# cpu-68008.net
KiCad netlist of a schematic drawn in EAGLE
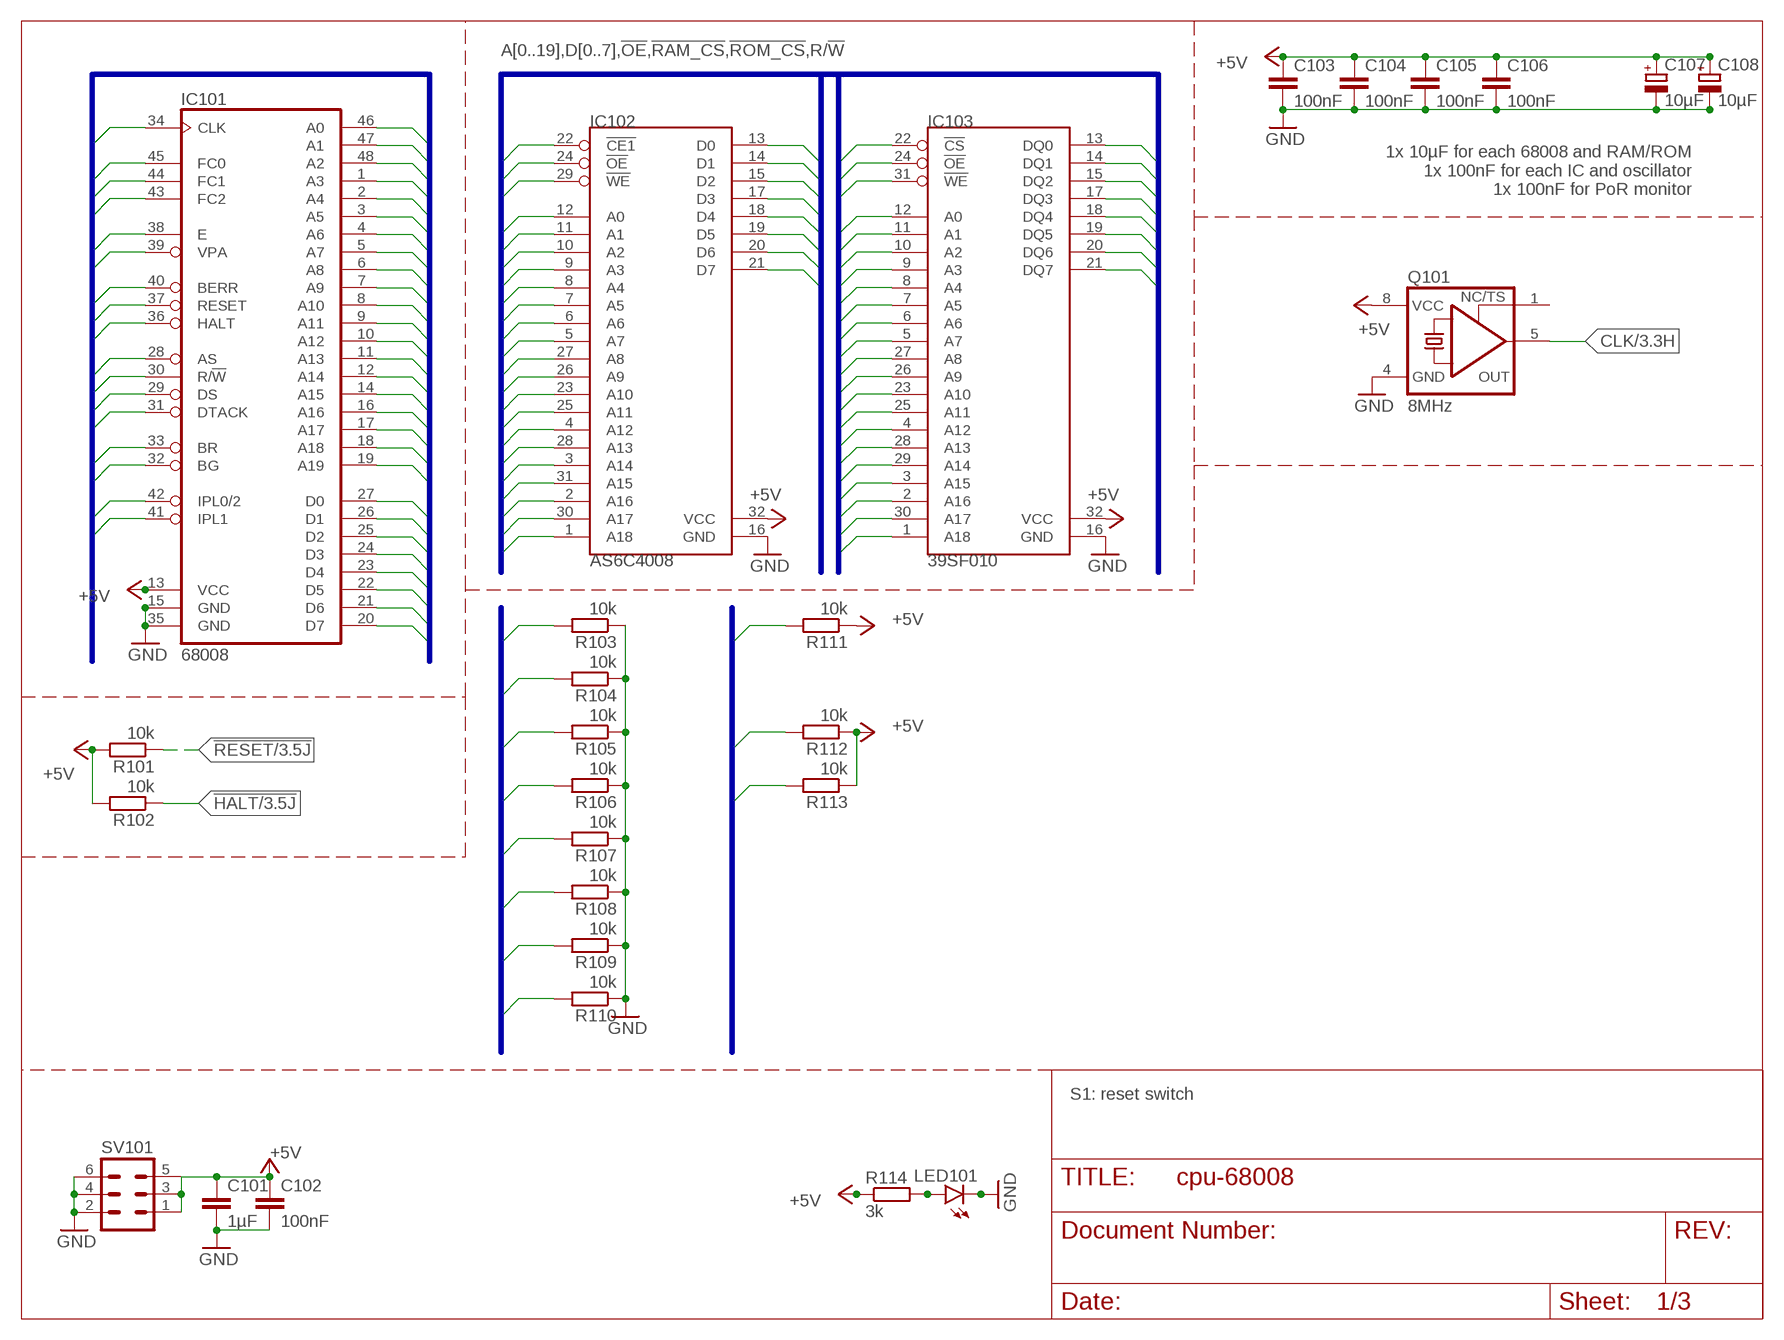
[diagram p0: schematic, sheet 1]
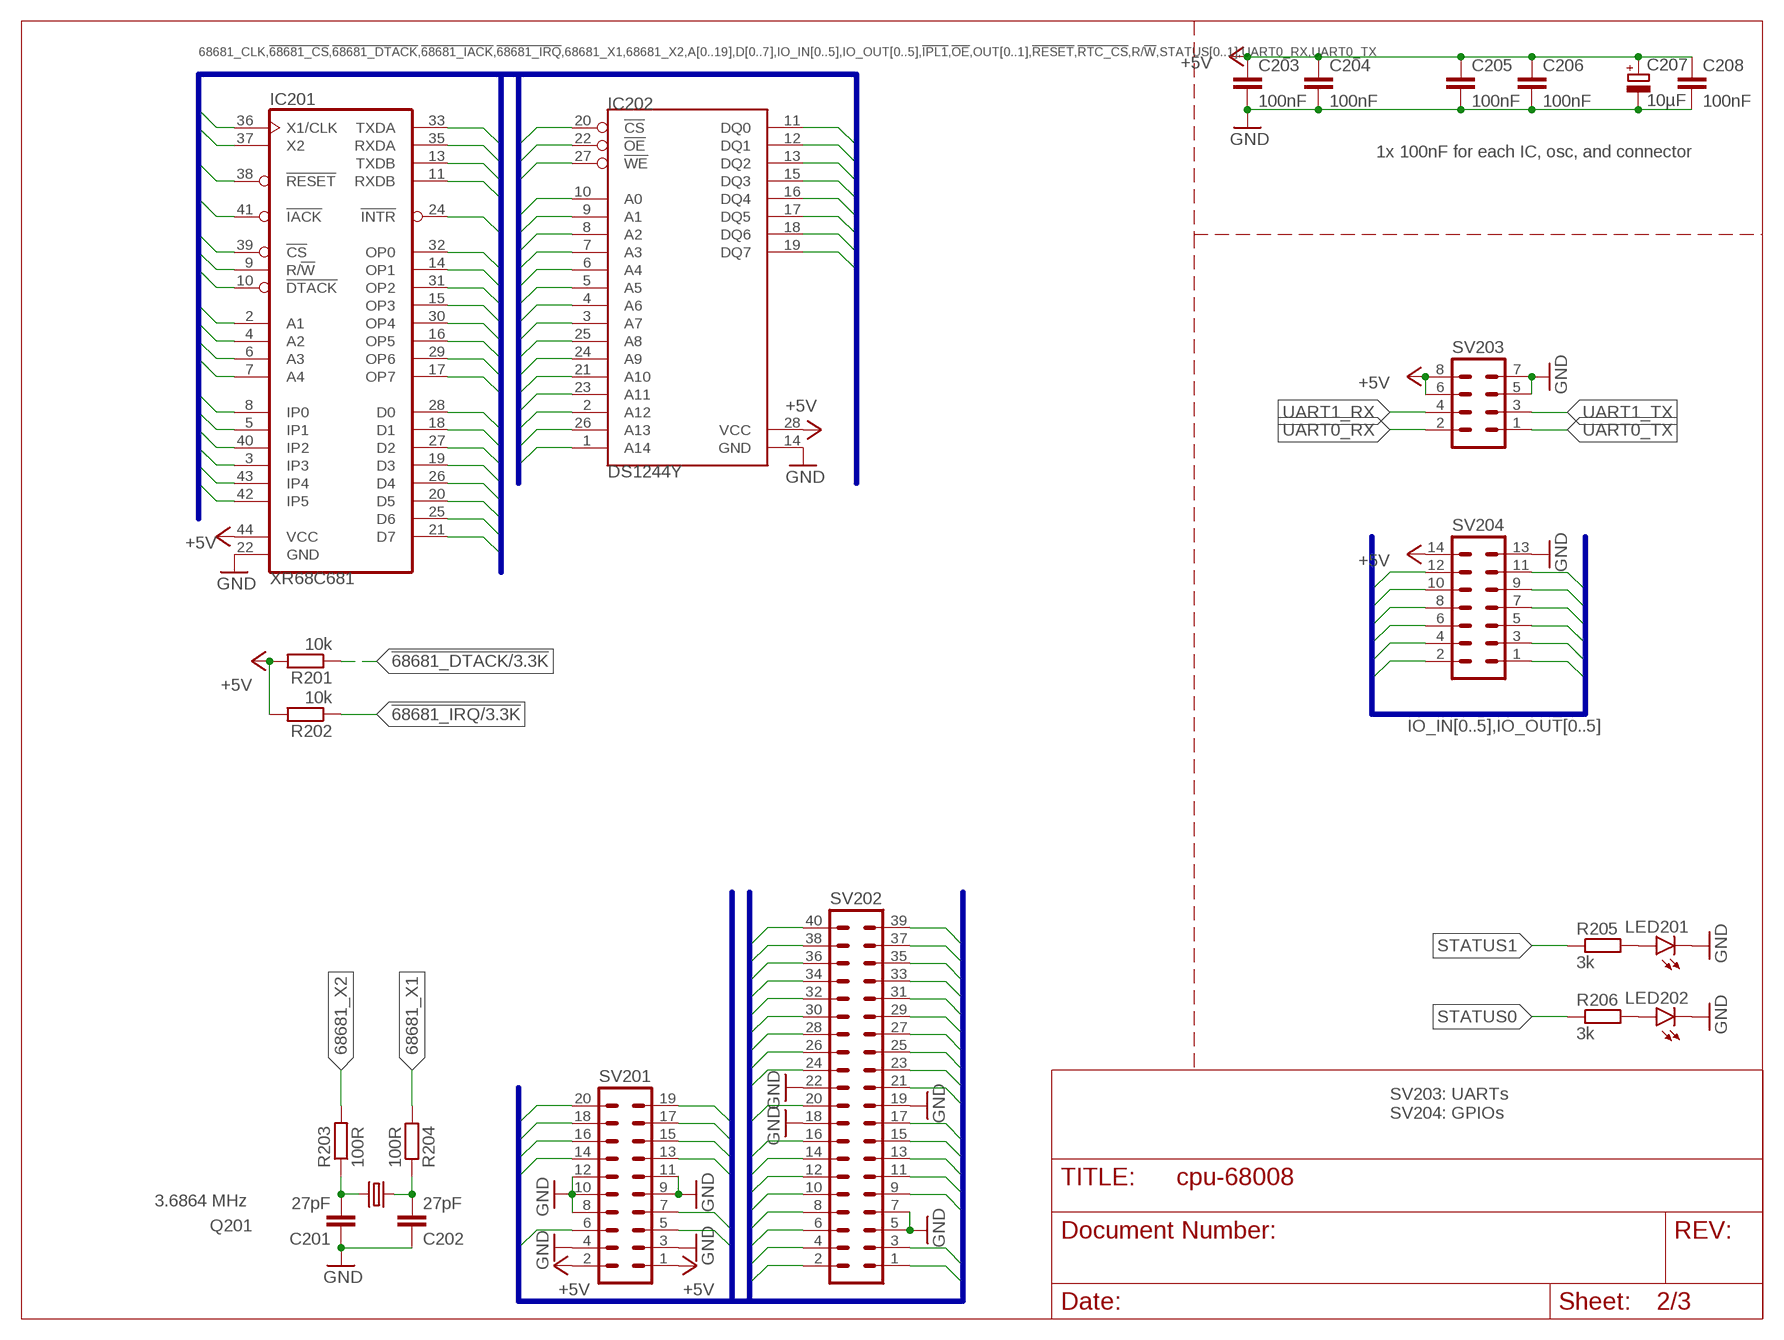
[diagram p1: schematic, sheet 2]
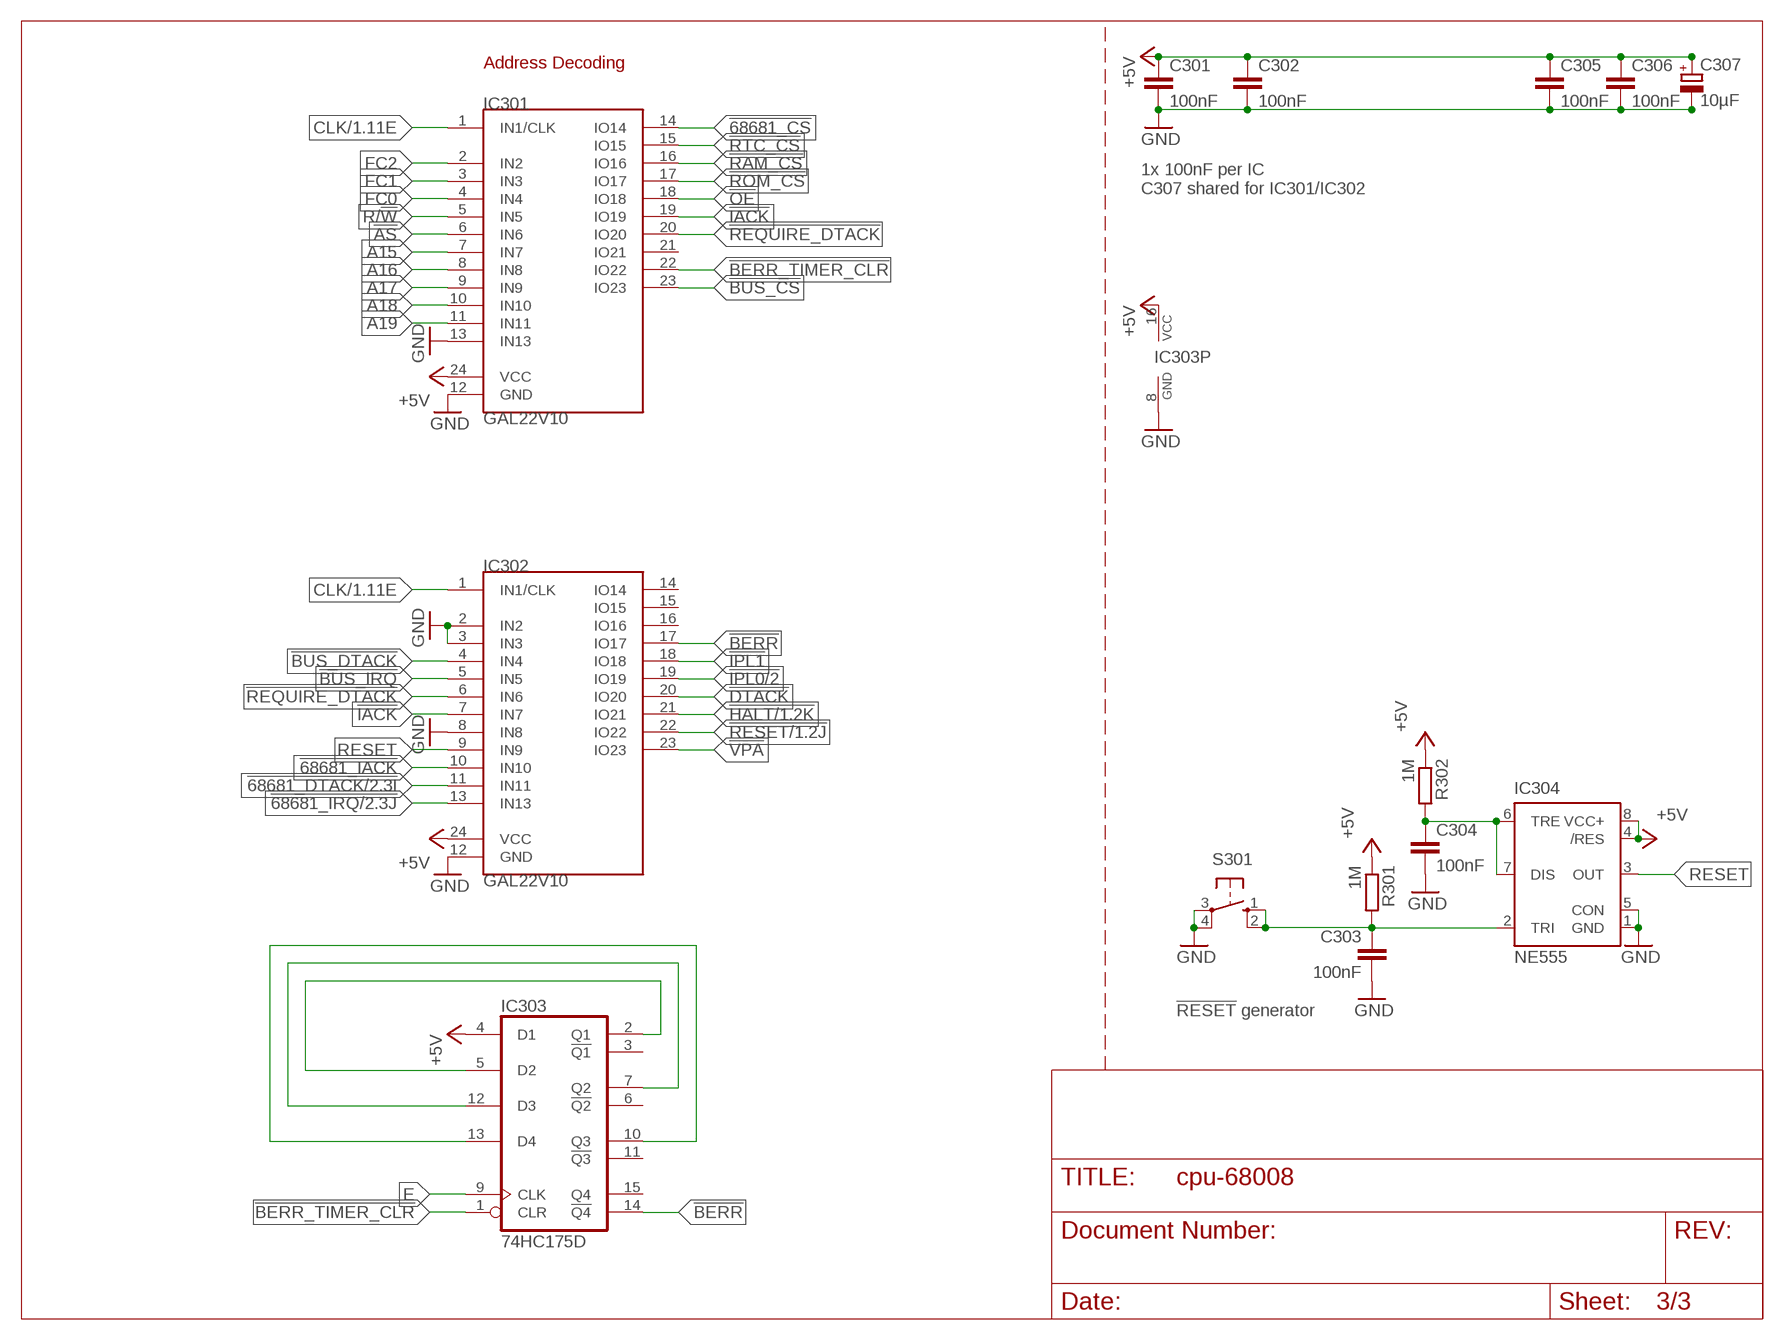
[diagram p2: schematic, sheet 3]

(export (version "E")
  (design (tool "Eeschema 10.0.6"))
  (components
    (comp (ref "C301")
      (value "100nF")
      (footprint "eagle-import:C0805")
      (libsource (lib "eagle-import") (part "C-EUC0805"))
    )
    (comp (ref "C302")
      (value "100nF")
      (footprint "eagle-import:C0805")
      (libsource (lib "eagle-import") (part "C-EUC0805"))
    )
    (comp (ref "C303")
      (value "100nF")
      (footprint "eagle-import:C0805")
      (libsource (lib "eagle-import") (part "C-EUC0805"))
    )
    (comp (ref "C304")
      (value "100nF")
      (footprint "eagle-import:C0805")
      (libsource (lib "eagle-import") (part "C-EUC0805"))
    )
    (comp (ref "C305")
      (value "100nF")
      (footprint "eagle-import:C0805")
      (libsource (lib "eagle-import") (part "C-EUC0805"))
    )
    (comp (ref "C306")
      (value "100nF")
      (footprint "eagle-import:C0805")
      (libsource (lib "eagle-import") (part "C-EUC0805"))
    )
    (comp (ref "C307")
      (value "10µF")
      (footprint "eagle-import:SMC_B")
      (libsource (lib "eagle-import") (part "CPOL-EUSMCB"))
    )
    (comp (ref "IC301")
      (value "GAL22V10")
      (footprint "eagle-import:DIL24S")
      (libsource (lib "eagle-import") (part "GAL22V10DIP24"))
    )
    (comp (ref "IC302")
      (value "GAL22V10")
      (footprint "eagle-import:DIL24S")
      (libsource (lib "eagle-import") (part "GAL22V10DIP24"))
    )
    (comp (ref "IC303")
      (value "74HC175D")
      (footprint "eagle-import:SO16")
      (libsource (lib "eagle-import") (part "74175DHC"))
    )
    (comp (ref "IC304")
      (value "NE555")
      (footprint "eagle-import:DIL-08")
      (fields (field (name "MF") "Arrow Electronics") (field (name "MPN") "NE555N"))
      (libsource (lib "eagle-import") (part "NE555"))
    )
    (comp (ref "R301")
      (value "1M")
      (footprint "eagle-import:R2012")
      (libsource (lib "eagle-import") (part "R-EU_R2012"))
    )
    (comp (ref "R302")
      (value "1M")
      (footprint "eagle-import:R2012")
      (libsource (lib "eagle-import") (part "R-EU_R2012"))
    )
    (comp (ref "S301")
      (value "10-XX")
      (footprint "eagle-import:B3F-10XX")
      (fields (field (name "MPN") "B3F-1000"))
      (libsource (lib "eagle-import") (part "10-XX"))
    )
    (comp (ref "C101")
      (value "1µF")
      (footprint "eagle-import:C0805")
      (libsource (lib "eagle-import") (part "C-EUC0805"))
    )
    (comp (ref "C102")
      (value "100nF")
      (footprint "eagle-import:C0805")
      (libsource (lib "eagle-import") (part "C-EUC0805"))
    )
    (comp (ref "C103")
      (value "100nF")
      (footprint "eagle-import:C0805")
      (libsource (lib "eagle-import") (part "C-EUC0805"))
    )
    (comp (ref "C104")
      (value "100nF")
      (footprint "eagle-import:C0805")
      (libsource (lib "eagle-import") (part "C-EUC0805"))
    )
    (comp (ref "C105")
      (value "100nF")
      (footprint "eagle-import:C0805")
      (libsource (lib "eagle-import") (part "C-EUC0805"))
    )
    (comp (ref "C106")
      (value "100nF")
      (footprint "eagle-import:C0805")
      (libsource (lib "eagle-import") (part "C-EUC0805"))
    )
    (comp (ref "C107")
      (value "10µF")
      (footprint "eagle-import:SMC_B")
      (libsource (lib "eagle-import") (part "CPOL-EUSMCB"))
    )
    (comp (ref "C108")
      (value "10µF")
      (footprint "eagle-import:SMC_B")
      (libsource (lib "eagle-import") (part "CPOL-EUSMCB"))
    )
    (comp (ref "IC101")
      (value "68008")
      (footprint "eagle-import:DIL48")
      (libsource (lib "eagle-import") (part "MC68008P"))
    )
    (comp (ref "IC102")
      (value "AS6C4008")
      (footprint "eagle-import:DIL32")
      (libsource (lib "eagle-import") (part "AS6C4008"))
    )
    (comp (ref "IC103")
      (value "39SF010")
      (footprint "eagle-import:DIL32")
      (fields (field (name "MOUSER") "804-39SF010A7CPHE"))
      (libsource (lib "eagle-import") (part "SST39SF0X0PDIP32"))
    )
    (comp (ref "LED101")
      (value "LEDCHIPLED_1206")
      (footprint "eagle-import:CHIPLED_1206")
      (libsource (lib "eagle-import") (part "LEDCHIPLED_1206"))
    )
    (comp (ref "Q101")
      (value "8MHz")
      (footprint "eagle-import:DIL08S")
      (libsource (lib "eagle-import") (part "XO-8"))
    )
    (comp (ref "R101")
      (value "10k")
      (footprint "eagle-import:R2012")
      (libsource (lib "eagle-import") (part "R-EU_R2012"))
    )
    (comp (ref "R102")
      (value "10k")
      (footprint "eagle-import:R2012")
      (libsource (lib "eagle-import") (part "R-EU_R2012"))
    )
    (comp (ref "R103")
      (value "10k")
      (footprint "eagle-import:R2012")
      (libsource (lib "eagle-import") (part "R-EU_R2012"))
    )
    (comp (ref "R104")
      (value "10k")
      (footprint "eagle-import:R2012")
      (libsource (lib "eagle-import") (part "R-EU_R2012"))
    )
    (comp (ref "R105")
      (value "10k")
      (footprint "eagle-import:R2012")
      (libsource (lib "eagle-import") (part "R-EU_R2012"))
    )
    (comp (ref "R106")
      (value "10k")
      (footprint "eagle-import:R2012")
      (libsource (lib "eagle-import") (part "R-EU_R2012"))
    )
    (comp (ref "R107")
      (value "10k")
      (footprint "eagle-import:R2012")
      (libsource (lib "eagle-import") (part "R-EU_R2012"))
    )
    (comp (ref "R108")
      (value "10k")
      (footprint "eagle-import:R2012")
      (libsource (lib "eagle-import") (part "R-EU_R2012"))
    )
    (comp (ref "R109")
      (value "10k")
      (footprint "eagle-import:R2012")
      (libsource (lib "eagle-import") (part "R-EU_R2012"))
    )
    (comp (ref "R110")
      (value "10k")
      (footprint "eagle-import:R2012")
      (libsource (lib "eagle-import") (part "R-EU_R2012"))
    )
    (comp (ref "R111")
      (value "10k")
      (footprint "eagle-import:R2012")
      (libsource (lib "eagle-import") (part "R-EU_R2012"))
    )
    (comp (ref "R112")
      (value "10k")
      (footprint "eagle-import:R2012")
      (libsource (lib "eagle-import") (part "R-EU_R2012"))
    )
    (comp (ref "R113")
      (value "10k")
      (footprint "eagle-import:R2012")
      (libsource (lib "eagle-import") (part "R-EU_R2012"))
    )
    (comp (ref "R114")
      (value "3k")
      (footprint "eagle-import:R2012")
      (libsource (lib "eagle-import") (part "R-EU_R2012"))
    )
    (comp (ref "SV101")
      (value "MA03-2")
      (footprint "eagle-import:MA03-2")
      (libsource (lib "eagle-import") (part "MA03-2"))
    )
    (comp (ref "C201")
      (value "27pF")
      (footprint "eagle-import:C0805")
      (libsource (lib "eagle-import") (part "C-EUC0805"))
    )
    (comp (ref "C202")
      (value "27pF")
      (footprint "eagle-import:C0805")
      (libsource (lib "eagle-import") (part "C-EUC0805"))
    )
    (comp (ref "C203")
      (value "100nF")
      (footprint "eagle-import:C0805")
      (libsource (lib "eagle-import") (part "C-EUC0805"))
    )
    (comp (ref "C204")
      (value "100nF")
      (footprint "eagle-import:C0805")
      (libsource (lib "eagle-import") (part "C-EUC0805"))
    )
    (comp (ref "C205")
      (value "100nF")
      (footprint "eagle-import:C0805")
      (libsource (lib "eagle-import") (part "C-EUC0805"))
    )
    (comp (ref "C206")
      (value "100nF")
      (footprint "eagle-import:C0805")
      (libsource (lib "eagle-import") (part "C-EUC0805"))
    )
    (comp (ref "C207")
      (value "10µF")
      (footprint "eagle-import:SMC_B")
      (libsource (lib "eagle-import") (part "CPOL-EUSMCB"))
    )
    (comp (ref "C208")
      (value "100nF")
      (footprint "eagle-import:C0805")
      (libsource (lib "eagle-import") (part "C-EUC0805"))
    )
    (comp (ref "IC201")
      (value "XR68C681")
      (footprint "eagle-import:PLCC-S44")
      (libsource (lib "eagle-import") (part "MC68681PLCC44-SOCKET"))
    )
    (comp (ref "IC202")
      (value "DS1244Y")
      (footprint "eagle-import:DIL28-6")
      (libsource (lib "eagle-import") (part "DS1244EDIP-28"))
    )
    (comp (ref "LED201")
      (value "LEDCHIPLED_1206")
      (footprint "eagle-import:CHIPLED_1206")
      (libsource (lib "eagle-import") (part "LEDCHIPLED_1206"))
    )
    (comp (ref "LED202")
      (value "LEDCHIPLED_1206")
      (footprint "eagle-import:CHIPLED_1206")
      (libsource (lib "eagle-import") (part "LEDCHIPLED_1206"))
    )
    (comp (ref "Q201")
      (value "3.6864 MHz")
      (footprint "eagle-import:HC49_S")
      (libsource (lib "eagle-import") (part "CRYSTALHC49S"))
    )
    (comp (ref "R201")
      (value "10k")
      (footprint "eagle-import:R2012")
      (libsource (lib "eagle-import") (part "R-EU_R2012"))
    )
    (comp (ref "R202")
      (value "10k")
      (footprint "eagle-import:R2012")
      (libsource (lib "eagle-import") (part "R-EU_R2012"))
    )
    (comp (ref "R203")
      (value "100R")
      (footprint "eagle-import:R2012")
      (libsource (lib "eagle-import") (part "R-EU_R2012"))
    )
    (comp (ref "R204")
      (value "100R")
      (footprint "eagle-import:R2012")
      (libsource (lib "eagle-import") (part "R-EU_R2012"))
    )
    (comp (ref "R205")
      (value "3k")
      (footprint "eagle-import:R2012")
      (libsource (lib "eagle-import") (part "R-EU_R2012"))
    )
    (comp (ref "R206")
      (value "3k")
      (footprint "eagle-import:R2012")
      (libsource (lib "eagle-import") (part "R-EU_R2012"))
    )
    (comp (ref "SV201")
      (value "MA10-2W")
      (footprint "eagle-import:MA10-2W")
      (libsource (lib "eagle-import") (part "MA10-2W"))
    )
    (comp (ref "SV202")
      (value "MA20-2W")
      (footprint "eagle-import:MA20-2W")
      (libsource (lib "eagle-import") (part "MA20-2W"))
    )
    (comp (ref "SV203")
      (value "MA04-2")
      (footprint "eagle-import:MA04-2")
      (libsource (lib "eagle-import") (part "MA04-2"))
    )
    (comp (ref "SV204")
      (value "MA07-2")
      (footprint "eagle-import:MA07-2")
      (libsource (lib "eagle-import") (part "MA07-2"))
    )
  )
  (nets
    (net (code "3") (name "+5V") (class "Default")
      (node (ref "C101") (pin "1") (pinfunction "1_1") (pintype "passive"))
      (node (ref "C102") (pin "1") (pinfunction "1_1") (pintype "passive"))
      (node (ref "C103") (pin "1") (pinfunction "1_1") (pintype "passive"))
      (node (ref "C104") (pin "1") (pinfunction "1_1") (pintype "passive"))
      (node (ref "C105") (pin "1") (pinfunction "1_1") (pintype "passive"))
      (node (ref "C106") (pin "1") (pinfunction "1_1") (pintype "passive"))
      (node (ref "C107") (pin "+") (pinfunction "+_+") (pintype "passive"))
      (node (ref "C108") (pin "+") (pinfunction "+_+") (pintype "passive"))
      (node (ref "C203") (pin "1") (pinfunction "1_1") (pintype "passive"))
      (node (ref "C204") (pin "1") (pinfunction "1_1") (pintype "passive"))
      (node (ref "C205") (pin "1") (pinfunction "1_1") (pintype "passive"))
      (node (ref "C206") (pin "1") (pinfunction "1_1") (pintype "passive"))
      (node (ref "C207") (pin "+") (pinfunction "+_+") (pintype "passive"))
      (node (ref "C208") (pin "1") (pinfunction "1_1") (pintype "passive"))
      (node (ref "C301") (pin "1") (pinfunction "1_1") (pintype "passive"))
      (node (ref "C302") (pin "1") (pinfunction "1_1") (pintype "passive"))
      (node (ref "C305") (pin "1") (pinfunction "1_1") (pintype "passive"))
      (node (ref "C306") (pin "1") (pinfunction "1_1") (pintype "passive"))
      (node (ref "C307") (pin "+") (pinfunction "+_+") (pintype "passive"))
      (node (ref "IC101") (pin "13") (pinfunction "VCC_13") (pintype "power_in"))
      (node (ref "IC102") (pin "32") (pinfunction "VCC_32") (pintype "power_in"))
      (node (ref "IC103") (pin "32") (pinfunction "VCC_32") (pintype "power_in"))
      (node (ref "IC201") (pin "44") (pinfunction "VCC_44") (pintype "power_in"))
      (node (ref "IC202") (pin "28") (pinfunction "VCC_28") (pintype "power_in"))
      (node (ref "IC301") (pin "24") (pinfunction "VCC_24") (pintype "power_in"))
      (node (ref "IC302") (pin "24") (pinfunction "VCC_24") (pintype "power_in"))
      (node (ref "IC303") (pin "16") (pinfunction "VCC_16") (pintype "power_in"))
      (node (ref "IC303") (pin "4") (pinfunction "D1_4") (pintype "input"))
      (node (ref "IC304") (pin "4") (pinfunction "/RES_4") (pintype "input"))
      (node (ref "IC304") (pin "8") (pinfunction "VCC+_8") (pintype "power_in"))
      (node (ref "Q101") (pin "8") (pinfunction "VCC_8") (pintype "power_in"))
      (node (ref "R101") (pin "2") (pinfunction "2_2") (pintype "passive"))
      (node (ref "R102") (pin "2") (pinfunction "2_2") (pintype "passive"))
      (node (ref "R111") (pin "1") (pinfunction "1_1") (pintype "passive"))
      (node (ref "R112") (pin "1") (pinfunction "1_1") (pintype "passive"))
      (node (ref "R113") (pin "1") (pinfunction "1_1") (pintype "passive"))
      (node (ref "R114") (pin "1") (pinfunction "1_1") (pintype "passive"))
      (node (ref "R201") (pin "2") (pinfunction "2_2") (pintype "passive"))
      (node (ref "R202") (pin "2") (pinfunction "2_2") (pintype "passive"))
      (node (ref "R301") (pin "1") (pinfunction "1_1") (pintype "passive"))
      (node (ref "R302") (pin "1") (pinfunction "1_1") (pintype "passive"))
      (node (ref "SV101") (pin "1") (pinfunction "1_1") (pintype "passive"))
      (node (ref "SV101") (pin "3") (pinfunction "3_3") (pintype "passive"))
      (node (ref "SV101") (pin "5") (pinfunction "5_5") (pintype "passive"))
      (node (ref "SV201") (pin "1") (pinfunction "1_1") (pintype "passive"))
      (node (ref "SV201") (pin "2") (pinfunction "2_2") (pintype "passive"))
      (node (ref "SV203") (pin "6") (pinfunction "6_6") (pintype "passive"))
      (node (ref "SV203") (pin "8") (pinfunction "8_8") (pintype "passive"))
      (node (ref "SV204") (pin "14") (pinfunction "14_14") (pintype "passive"))
    )
    (net (code "7") (name "68681_X1") (class "Default")
      (node (ref "IC201") (pin "36") (pinfunction "X1/CLK_36") (pintype "input"))
      (node (ref "R204") (pin "2") (pinfunction "2_2") (pintype "passive"))
    )
    (net (code "8") (name "68681_X2") (class "Default")
      (node (ref "IC201") (pin "37") (pinfunction "X2_37") (pintype "output"))
      (node (ref "R203") (pin "2") (pinfunction "2_2") (pintype "passive"))
    )
    (net (code "9") (name "A0") (class "Default")
      (node (ref "IC101") (pin "46") (pinfunction "A0_46") (pintype "output"))
      (node (ref "IC102") (pin "12") (pinfunction "A0_12") (pintype "input"))
      (node (ref "IC103") (pin "12") (pinfunction "A0_12") (pintype "input"))
      (node (ref "IC201") (pin "2") (pinfunction "A1_2") (pintype "input"))
      (node (ref "IC202") (pin "10") (pinfunction "A0_10") (pintype "input"))
      (node (ref "SV201") (pin "17") (pinfunction "17_17") (pintype "passive"))
    )
    (net (code "10") (name "A1") (class "Default")
      (node (ref "IC101") (pin "47") (pinfunction "A1_47") (pintype "output"))
      (node (ref "IC102") (pin "11") (pinfunction "A1_11") (pintype "input"))
      (node (ref "IC103") (pin "11") (pinfunction "A1_11") (pintype "input"))
      (node (ref "IC201") (pin "4") (pinfunction "A2_4") (pintype "input"))
      (node (ref "IC202") (pin "9") (pinfunction "A1_9") (pintype "input"))
      (node (ref "SV201") (pin "15") (pinfunction "15_15") (pintype "passive"))
    )
    (net (code "11") (name "A2") (class "Default")
      (node (ref "IC101") (pin "48") (pinfunction "A2_48") (pintype "output"))
      (node (ref "IC102") (pin "10") (pinfunction "A2_10") (pintype "input"))
      (node (ref "IC103") (pin "10") (pinfunction "A2_10") (pintype "input"))
      (node (ref "IC201") (pin "6") (pinfunction "A3_6") (pintype "input"))
      (node (ref "IC202") (pin "8") (pinfunction "A2_8") (pintype "input"))
      (node (ref "SV201") (pin "13") (pinfunction "13_13") (pintype "passive"))
    )
    (net (code "12") (name "A3") (class "Default")
      (node (ref "IC101") (pin "1") (pinfunction "A3_1") (pintype "output"))
      (node (ref "IC102") (pin "9") (pinfunction "A3_9") (pintype "input"))
      (node (ref "IC103") (pin "9") (pinfunction "A3_9") (pintype "input"))
      (node (ref "IC201") (pin "7") (pinfunction "A4_7") (pintype "input"))
      (node (ref "IC202") (pin "7") (pinfunction "A3_7") (pintype "input"))
      (node (ref "SV201") (pin "14") (pinfunction "14_14") (pintype "passive"))
    )
    (net (code "13") (name "A4") (class "Default")
      (node (ref "IC101") (pin "2") (pinfunction "A4_2") (pintype "output"))
      (node (ref "IC102") (pin "8") (pinfunction "A4_8") (pintype "input"))
      (node (ref "IC103") (pin "8") (pinfunction "A4_8") (pintype "input"))
      (node (ref "IC202") (pin "6") (pinfunction "A4_6") (pintype "input"))
      (node (ref "SV201") (pin "16") (pinfunction "16_16") (pintype "passive"))
    )
    (net (code "14") (name "A5") (class "Default")
      (node (ref "IC101") (pin "3") (pinfunction "A5_3") (pintype "output"))
      (node (ref "IC102") (pin "7") (pinfunction "A5_7") (pintype "input"))
      (node (ref "IC103") (pin "7") (pinfunction "A5_7") (pintype "input"))
      (node (ref "IC202") (pin "5") (pinfunction "A5_5") (pintype "input"))
      (node (ref "SV201") (pin "18") (pinfunction "18_18") (pintype "passive"))
    )
    (net (code "15") (name "A6") (class "Default")
      (node (ref "IC101") (pin "4") (pinfunction "A6_4") (pintype "output"))
      (node (ref "IC102") (pin "6") (pinfunction "A6_6") (pintype "input"))
      (node (ref "IC103") (pin "6") (pinfunction "A6_6") (pintype "input"))
      (node (ref "IC202") (pin "4") (pinfunction "A6_4") (pintype "input"))
      (node (ref "SV201") (pin "20") (pinfunction "20_20") (pintype "passive"))
    )
    (net (code "16") (name "A7") (class "Default")
      (node (ref "IC101") (pin "5") (pinfunction "A7_5") (pintype "output"))
      (node (ref "IC102") (pin "5") (pinfunction "A7_5") (pintype "input"))
      (node (ref "IC103") (pin "5") (pinfunction "A7_5") (pintype "input"))
      (node (ref "IC202") (pin "3") (pinfunction "A7_3") (pintype "input"))
      (node (ref "SV202") (pin "2") (pinfunction "2_2") (pintype "passive"))
    )
    (net (code "17") (name "A8") (class "Default")
      (node (ref "IC101") (pin "6") (pinfunction "A8_6") (pintype "output"))
      (node (ref "IC102") (pin "27") (pinfunction "A8_27") (pintype "input"))
      (node (ref "IC103") (pin "27") (pinfunction "A8_27") (pintype "input"))
      (node (ref "IC202") (pin "25") (pinfunction "A8_25") (pintype "input"))
      (node (ref "SV202") (pin "4") (pinfunction "4_4") (pintype "passive"))
    )
    (net (code "18") (name "A9") (class "Default")
      (node (ref "IC101") (pin "7") (pinfunction "A9_7") (pintype "output"))
      (node (ref "IC102") (pin "26") (pinfunction "A9_26") (pintype "input"))
      (node (ref "IC103") (pin "26") (pinfunction "A9_26") (pintype "input"))
      (node (ref "IC202") (pin "24") (pinfunction "A9_24") (pintype "input"))
      (node (ref "SV202") (pin "6") (pinfunction "6_6") (pintype "passive"))
    )
    (net (code "19") (name "A10") (class "Default")
      (node (ref "IC101") (pin "8") (pinfunction "A10_8") (pintype "output"))
      (node (ref "IC102") (pin "23") (pinfunction "A10_23") (pintype "input"))
      (node (ref "IC103") (pin "23") (pinfunction "A10_23") (pintype "input"))
      (node (ref "IC202") (pin "21") (pinfunction "A10_21") (pintype "input"))
      (node (ref "SV202") (pin "8") (pinfunction "8_8") (pintype "passive"))
    )
    (net (code "20") (name "A11") (class "Default")
      (node (ref "IC101") (pin "9") (pinfunction "A11_9") (pintype "output"))
      (node (ref "IC102") (pin "25") (pinfunction "A11_25") (pintype "input"))
      (node (ref "IC103") (pin "25") (pinfunction "A11_25") (pintype "input"))
      (node (ref "IC202") (pin "23") (pinfunction "A11_23") (pintype "input"))
      (node (ref "SV202") (pin "10") (pinfunction "10_10") (pintype "passive"))
    )
    (net (code "21") (name "A12") (class "Default")
      (node (ref "IC101") (pin "10") (pinfunction "A12_10") (pintype "output"))
      (node (ref "IC102") (pin "4") (pinfunction "A12_4") (pintype "input"))
      (node (ref "IC103") (pin "4") (pinfunction "A12_4") (pintype "input"))
      (node (ref "IC202") (pin "2") (pinfunction "A12_2") (pintype "input"))
      (node (ref "SV202") (pin "12") (pinfunction "12_12") (pintype "passive"))
    )
    (net (code "22") (name "A13") (class "Default")
      (node (ref "IC101") (pin "11") (pinfunction "A13_11") (pintype "output"))
      (node (ref "IC102") (pin "28") (pinfunction "A13_28") (pintype "input"))
      (node (ref "IC103") (pin "28") (pinfunction "A13_28") (pintype "input"))
      (node (ref "IC202") (pin "26") (pinfunction "A13_26") (pintype "input"))
      (node (ref "SV202") (pin "14") (pinfunction "14_14") (pintype "passive"))
    )
    (net (code "23") (name "A14") (class "Default")
      (node (ref "IC101") (pin "12") (pinfunction "A14_12") (pintype "output"))
      (node (ref "IC102") (pin "3") (pinfunction "A14_3") (pintype "input"))
      (node (ref "IC103") (pin "29") (pinfunction "A14_29") (pintype "input"))
      (node (ref "IC202") (pin "1") (pinfunction "A14_1") (pintype "input"))
      (node (ref "SV202") (pin "16") (pinfunction "16_16") (pintype "passive"))
    )
    (net (code "24") (name "A15") (class "Default")
      (node (ref "IC101") (pin "14") (pinfunction "A15_14") (pintype "output"))
      (node (ref "IC102") (pin "31") (pinfunction "A15_31") (pintype "input"))
      (node (ref "IC103") (pin "3") (pinfunction "A15_3") (pintype "input"))
      (node (ref "IC301") (pin "7") (pinfunction "IN7_7") (pintype "input"))
      (node (ref "SV202") (pin "20") (pinfunction "20_20") (pintype "passive"))
    )
    (net (code "25") (name "A16") (class "Default")
      (node (ref "IC101") (pin "16") (pinfunction "A16_16") (pintype "output"))
      (node (ref "IC102") (pin "2") (pinfunction "A16_2") (pintype "input"))
      (node (ref "IC103") (pin "2") (pinfunction "A16_2") (pintype "input"))
      (node (ref "IC301") (pin "8") (pinfunction "IN8_8") (pintype "input"))
      (node (ref "SV202") (pin "24") (pinfunction "24_24") (pintype "passive"))
    )
    (net (code "26") (name "A17") (class "Default")
      (node (ref "IC101") (pin "17") (pinfunction "A17_17") (pintype "output"))
      (node (ref "IC102") (pin "30") (pinfunction "A17_30") (pintype "input"))
      (node (ref "IC103") (pin "30") (pinfunction "A17_30") (pintype "input"))
      (node (ref "IC301") (pin "9") (pinfunction "IN9_9") (pintype "input"))
      (node (ref "SV202") (pin "26") (pinfunction "26_26") (pintype "passive"))
    )
    (net (code "27") (name "A18") (class "Default")
      (node (ref "IC101") (pin "18") (pinfunction "A18_18") (pintype "output"))
      (node (ref "IC102") (pin "1") (pinfunction "A18_1") (pintype "input"))
      (node (ref "IC103") (pin "1") (pinfunction "A18_1") (pintype "input"))
      (node (ref "IC301") (pin "10") (pinfunction "IN10_10") (pintype "input"))
      (node (ref "SV202") (pin "28") (pinfunction "28_28") (pintype "passive"))
    )
    (net (code "28") (name "A19") (class "Default")
      (node (ref "IC101") (pin "19") (pinfunction "A19_19") (pintype "output"))
      (node (ref "IC301") (pin "11") (pinfunction "IN11_11") (pintype "input"))
      (node (ref "SV202") (pin "30") (pinfunction "30_30") (pintype "passive"))
    )
    (net (code "29") (name "CLK") (class "Default")
      (node (ref "IC101") (pin "34") (pinfunction "CLK_34") (pintype "input"))
      (node (ref "IC301") (pin "1") (pinfunction "IN1/CLK_1") (pintype "input"))
      (node (ref "IC302") (pin "1") (pinfunction "IN1/CLK_1") (pintype "input"))
      (node (ref "Q101") (pin "5") (pinfunction "OUT_5") (pintype "output"))
      (node (ref "SV202") (pin "21") (pinfunction "21_21") (pintype "passive"))
    )
    (net (code "30") (name "D0") (class "Default")
      (node (ref "IC101") (pin "27") (pinfunction "D0_27") (pintype "bidirectional"))
      (node (ref "IC102") (pin "13") (pinfunction "D0_13") (pintype "bidirectional"))
      (node (ref "IC103") (pin "13") (pinfunction "DQ0_13") (pintype "bidirectional"))
      (node (ref "IC201") (pin "28") (pinfunction "D0_28") (pintype "bidirectional"))
      (node (ref "IC202") (pin "11") (pinfunction "DQ0_11") (pintype "bidirectional"))
      (node (ref "R103") (pin "2") (pinfunction "2_2") (pintype "passive"))
      (node (ref "SV202") (pin "35") (pinfunction "35_35") (pintype "passive"))
    )
    (net (code "31") (name "D1") (class "Default")
      (node (ref "IC101") (pin "26") (pinfunction "D1_26") (pintype "bidirectional"))
      (node (ref "IC102") (pin "14") (pinfunction "D1_14") (pintype "bidirectional"))
      (node (ref "IC103") (pin "14") (pinfunction "DQ1_14") (pintype "bidirectional"))
      (node (ref "IC201") (pin "18") (pinfunction "D1_18") (pintype "bidirectional"))
      (node (ref "IC202") (pin "12") (pinfunction "DQ1_12") (pintype "bidirectional"))
      (node (ref "R104") (pin "2") (pinfunction "2_2") (pintype "passive"))
      (node (ref "SV202") (pin "37") (pinfunction "37_37") (pintype "passive"))
    )
    (net (code "32") (name "D2") (class "Default")
      (node (ref "IC101") (pin "25") (pinfunction "D2_25") (pintype "bidirectional"))
      (node (ref "IC102") (pin "15") (pinfunction "D2_15") (pintype "bidirectional"))
      (node (ref "IC103") (pin "15") (pinfunction "DQ2_15") (pintype "bidirectional"))
      (node (ref "IC201") (pin "27") (pinfunction "D2_27") (pintype "bidirectional"))
      (node (ref "IC202") (pin "13") (pinfunction "DQ2_13") (pintype "bidirectional"))
      (node (ref "R105") (pin "2") (pinfunction "2_2") (pintype "passive"))
      (node (ref "SV202") (pin "39") (pinfunction "39_39") (pintype "passive"))
    )
    (net (code "33") (name "D3") (class "Default")
      (node (ref "IC101") (pin "24") (pinfunction "D3_24") (pintype "bidirectional"))
      (node (ref "IC102") (pin "17") (pinfunction "D3_17") (pintype "bidirectional"))
      (node (ref "IC103") (pin "17") (pinfunction "DQ3_17") (pintype "bidirectional"))
      (node (ref "IC201") (pin "19") (pinfunction "D3_19") (pintype "bidirectional"))
      (node (ref "IC202") (pin "15") (pinfunction "DQ3_15") (pintype "bidirectional"))
      (node (ref "R106") (pin "2") (pinfunction "2_2") (pintype "passive"))
      (node (ref "SV202") (pin "40") (pinfunction "40_40") (pintype "passive"))
    )
    (net (code "34") (name "D4") (class "Default")
      (node (ref "IC101") (pin "23") (pinfunction "D4_23") (pintype "bidirectional"))
      (node (ref "IC102") (pin "18") (pinfunction "D4_18") (pintype "bidirectional"))
      (node (ref "IC103") (pin "18") (pinfunction "DQ4_18") (pintype "bidirectional"))
      (node (ref "IC201") (pin "26") (pinfunction "D4_26") (pintype "bidirectional"))
      (node (ref "IC202") (pin "16") (pinfunction "DQ4_16") (pintype "bidirectional"))
      (node (ref "R107") (pin "2") (pinfunction "2_2") (pintype "passive"))
      (node (ref "SV202") (pin "38") (pinfunction "38_38") (pintype "passive"))
    )
    (net (code "35") (name "D5") (class "Default")
      (node (ref "IC101") (pin "22") (pinfunction "D5_22") (pintype "bidirectional"))
      (node (ref "IC102") (pin "19") (pinfunction "D5_19") (pintype "bidirectional"))
      (node (ref "IC103") (pin "19") (pinfunction "DQ5_19") (pintype "bidirectional"))
      (node (ref "IC201") (pin "20") (pinfunction "D5_20") (pintype "bidirectional"))
      (node (ref "IC202") (pin "17") (pinfunction "DQ5_17") (pintype "bidirectional"))
      (node (ref "R108") (pin "2") (pinfunction "2_2") (pintype "passive"))
      (node (ref "SV202") (pin "36") (pinfunction "36_36") (pintype "passive"))
    )
    (net (code "36") (name "D6") (class "Default")
      (node (ref "IC101") (pin "21") (pinfunction "D6_21") (pintype "bidirectional"))
      (node (ref "IC102") (pin "20") (pinfunction "D6_20") (pintype "bidirectional"))
      (node (ref "IC103") (pin "20") (pinfunction "DQ6_20") (pintype "bidirectional"))
      (node (ref "IC201") (pin "25") (pinfunction "D6_25") (pintype "bidirectional"))
      (node (ref "IC202") (pin "18") (pinfunction "DQ6_18") (pintype "bidirectional"))
      (node (ref "R109") (pin "2") (pinfunction "2_2") (pintype "passive"))
      (node (ref "SV202") (pin "34") (pinfunction "34_34") (pintype "passive"))
    )
    (net (code "37") (name "D7") (class "Default")
      (node (ref "IC101") (pin "20") (pinfunction "D7_20") (pintype "bidirectional"))
      (node (ref "IC102") (pin "21") (pinfunction "D7_21") (pintype "bidirectional"))
      (node (ref "IC103") (pin "21") (pinfunction "DQ7_21") (pintype "bidirectional"))
      (node (ref "IC201") (pin "21") (pinfunction "D7_21") (pintype "bidirectional"))
      (node (ref "IC202") (pin "19") (pinfunction "DQ7_19") (pintype "bidirectional"))
      (node (ref "R110") (pin "2") (pinfunction "2_2") (pintype "passive"))
      (node (ref "SV202") (pin "32") (pinfunction "32_32") (pintype "passive"))
    )
    (net (code "38") (name "E") (class "Default")
      (node (ref "IC101") (pin "38") (pinfunction "E_38") (pintype "output"))
      (node (ref "IC303") (pin "9") (pinfunction "CLK_9") (pintype "input"))
      (node (ref "SV202") (pin "13") (pinfunction "13_13") (pintype "passive"))
    )
    (net (code "39") (name "FC0") (class "Default")
      (node (ref "IC101") (pin "45") (pinfunction "FC0_45") (pintype "output"))
      (node (ref "IC301") (pin "4") (pinfunction "IN4_4") (pintype "input"))
      (node (ref "SV201") (pin "19") (pinfunction "19_19") (pintype "passive"))
    )
    (net (code "40") (name "FC1") (class "Default")
      (node (ref "IC101") (pin "44") (pinfunction "FC1_44") (pintype "output"))
      (node (ref "IC301") (pin "3") (pinfunction "IN3_3") (pintype "input"))
      (node (ref "SV202") (pin "1") (pinfunction "1_1") (pintype "passive"))
    )
    (net (code "41") (name "FC2") (class "Default")
      (node (ref "IC101") (pin "43") (pinfunction "FC2_43") (pintype "output"))
      (node (ref "IC301") (pin "2") (pinfunction "IN2_2") (pintype "input"))
      (node (ref "SV202") (pin "3") (pinfunction "3_3") (pintype "passive"))
    )
    (net (code "42") (name "GND") (class "Default")
      (node (ref "C101") (pin "2") (pinfunction "2_2") (pintype "passive"))
      (node (ref "C102") (pin "2") (pinfunction "2_2") (pintype "passive"))
      (node (ref "C103") (pin "2") (pinfunction "2_2") (pintype "passive"))
      (node (ref "C104") (pin "2") (pinfunction "2_2") (pintype "passive"))
      (node (ref "C105") (pin "2") (pinfunction "2_2") (pintype "passive"))
      (node (ref "C106") (pin "2") (pinfunction "2_2") (pintype "passive"))
      (node (ref "C107") (pin "-") (pinfunction "-_-") (pintype "passive"))
      (node (ref "C108") (pin "-") (pinfunction "-_-") (pintype "passive"))
      (node (ref "C201") (pin "1") (pinfunction "1_1") (pintype "passive"))
      (node (ref "C202") (pin "1") (pinfunction "1_1") (pintype "passive"))
      (node (ref "C203") (pin "2") (pinfunction "2_2") (pintype "passive"))
      (node (ref "C204") (pin "2") (pinfunction "2_2") (pintype "passive"))
      (node (ref "C205") (pin "2") (pinfunction "2_2") (pintype "passive"))
      (node (ref "C206") (pin "2") (pinfunction "2_2") (pintype "passive"))
      (node (ref "C207") (pin "-") (pinfunction "-_-") (pintype "passive"))
      (node (ref "C208") (pin "2") (pinfunction "2_2") (pintype "passive"))
      (node (ref "C301") (pin "2") (pinfunction "2_2") (pintype "passive"))
      (node (ref "C302") (pin "2") (pinfunction "2_2") (pintype "passive"))
      (node (ref "C303") (pin "2") (pinfunction "2_2") (pintype "passive"))
      (node (ref "C304") (pin "2") (pinfunction "2_2") (pintype "passive"))
      (node (ref "C305") (pin "2") (pinfunction "2_2") (pintype "passive"))
      (node (ref "C306") (pin "2") (pinfunction "2_2") (pintype "passive"))
      (node (ref "C307") (pin "-") (pinfunction "-_-") (pintype "passive"))
      (node (ref "IC101") (pin "15") (pinfunction "GND_15") (pintype "power_in"))
      (node (ref "IC101") (pin "35") (pinfunction "GND_35") (pintype "power_in"))
      (node (ref "IC102") (pin "16") (pinfunction "GND_16") (pintype "power_in"))
      (node (ref "IC103") (pin "16") (pinfunction "GND_16") (pintype "power_in"))
      (node (ref "IC201") (pin "22") (pinfunction "GND_22") (pintype "power_in"))
      (node (ref "IC202") (pin "14") (pinfunction "GND_14") (pintype "power_in"))
      (node (ref "IC301") (pin "12") (pinfunction "GND_12") (pintype "power_in"))
      (node (ref "IC301") (pin "13") (pinfunction "IN13_13") (pintype "input"))
      (node (ref "IC302") (pin "12") (pinfunction "GND_12") (pintype "power_in"))
      (node (ref "IC302") (pin "2") (pinfunction "IN2_2") (pintype "input"))
      (node (ref "IC302") (pin "3") (pinfunction "IN3_3") (pintype "input"))
      (node (ref "IC302") (pin "8") (pinfunction "IN8_8") (pintype "input"))
      (node (ref "IC303") (pin "8") (pinfunction "GND_8") (pintype "power_in"))
      (node (ref "IC304") (pin "1") (pinfunction "GND_1") (pintype "power_in"))
      (node (ref "IC304") (pin "5") (pinfunction "CON_5") (pintype "input"))
      (node (ref "LED101") (pin "C") (pinfunction "C_C") (pintype "passive"))
      (node (ref "LED201") (pin "C") (pinfunction "C_C") (pintype "passive"))
      (node (ref "LED202") (pin "C") (pinfunction "C_C") (pintype "passive"))
      (node (ref "Q101") (pin "4") (pinfunction "GND_4") (pintype "power_in"))
      (node (ref "R103") (pin "1") (pinfunction "1_1") (pintype "passive"))
      (node (ref "R104") (pin "1") (pinfunction "1_1") (pintype "passive"))
      (node (ref "R105") (pin "1") (pinfunction "1_1") (pintype "passive"))
      (node (ref "R106") (pin "1") (pinfunction "1_1") (pintype "passive"))
      (node (ref "R107") (pin "1") (pinfunction "1_1") (pintype "passive"))
      (node (ref "R108") (pin "1") (pinfunction "1_1") (pintype "passive"))
      (node (ref "R109") (pin "1") (pinfunction "1_1") (pintype "passive"))
      (node (ref "R110") (pin "1") (pinfunction "1_1") (pintype "passive"))
      (node (ref "S301") (pin "3") (pinfunction "P_3") (pintype "passive"))
      (node (ref "S301") (pin "4") (pinfunction "P1_4") (pintype "passive"))
      (node (ref "SV101") (pin "2") (pinfunction "2_2") (pintype "passive"))
      (node (ref "SV101") (pin "4") (pinfunction "4_4") (pintype "passive"))
      (node (ref "SV101") (pin "6") (pinfunction "6_6") (pintype "passive"))
      (node (ref "SV201") (pin "10") (pinfunction "10_10") (pintype "passive"))
      (node (ref "SV201") (pin "11") (pinfunction "11_11") (pintype "passive"))
      (node (ref "SV201") (pin "12") (pinfunction "12_12") (pintype "passive"))
      (node (ref "SV201") (pin "3") (pinfunction "3_3") (pintype "passive"))
      (node (ref "SV201") (pin "4") (pinfunction "4_4") (pintype "passive"))
      (node (ref "SV201") (pin "8") (pinfunction "8_8") (pintype "passive"))
      (node (ref "SV201") (pin "9") (pinfunction "9_9") (pintype "passive"))
      (node (ref "SV202") (pin "18") (pinfunction "18_18") (pintype "passive"))
      (node (ref "SV202") (pin "19") (pinfunction "19_19") (pintype "passive"))
      (node (ref "SV202") (pin "22") (pinfunction "22_22") (pintype "passive"))
      (node (ref "SV202") (pin "5") (pinfunction "5_5") (pintype "passive"))
      (node (ref "SV202") (pin "7") (pinfunction "7_7") (pintype "passive"))
      (node (ref "SV203") (pin "5") (pinfunction "5_5") (pintype "passive"))
      (node (ref "SV203") (pin "7") (pinfunction "7_7") (pintype "passive"))
      (node (ref "SV204") (pin "13") (pinfunction "13_13") (pintype "passive"))
    )
    (net (code "43") (name "IO_IN0") (class "Default")
      (node (ref "IC201") (pin "40") (pinfunction "IP2_40") (pintype "input"))
      (node (ref "SV204") (pin "12") (pinfunction "12_12") (pintype "passive"))
    )
    (net (code "44") (name "IO_IN1") (class "Default")
      (node (ref "IC201") (pin "42") (pinfunction "IP5_42") (pintype "input"))
      (node (ref "SV204") (pin "10") (pinfunction "10_10") (pintype "passive"))
    )
    (net (code "45") (name "IO_IN2") (class "Default")
      (node (ref "IC201") (pin "43") (pinfunction "IP4_43") (pintype "input"))
      (node (ref "SV204") (pin "8") (pinfunction "8_8") (pintype "passive"))
    )
    (net (code "46") (name "IO_IN3") (class "Default")
      (node (ref "IC201") (pin "3") (pinfunction "IP3_3") (pintype "input"))
      (node (ref "SV204") (pin "6") (pinfunction "6_6") (pintype "passive"))
    )
    (net (code "47") (name "IO_IN4") (class "Default")
      (node (ref "IC201") (pin "5") (pinfunction "IP1_5") (pintype "input"))
      (node (ref "SV204") (pin "4") (pinfunction "4_4") (pintype "passive"))
    )
    (net (code "48") (name "IO_IN5") (class "Default")
      (node (ref "IC201") (pin "8") (pinfunction "IP0_8") (pintype "input"))
      (node (ref "SV204") (pin "2") (pinfunction "2_2") (pintype "passive"))
    )
    (net (code "49") (name "IO_OUT0") (class "Default")
      (node (ref "IC201") (pin "31") (pinfunction "OP2_31") (pintype "output"))
      (node (ref "SV204") (pin "11") (pinfunction "11_11") (pintype "passive"))
    )
    (net (code "50") (name "IO_OUT1") (class "Default")
      (node (ref "IC201") (pin "32") (pinfunction "OP0_32") (pintype "output"))
      (node (ref "SV204") (pin "9") (pinfunction "9_9") (pintype "passive"))
    )
    (net (code "51") (name "IO_OUT2") (class "Default")
      (node (ref "IC201") (pin "29") (pinfunction "OP6_29") (pintype "output"))
      (node (ref "SV204") (pin "7") (pinfunction "7_7") (pintype "passive"))
    )
    (net (code "52") (name "IO_OUT3") (class "Default")
      (node (ref "IC201") (pin "30") (pinfunction "OP4_30") (pintype "output"))
      (node (ref "SV204") (pin "5") (pinfunction "5_5") (pintype "passive"))
    )
    (net (code "53") (name "IO_OUT4") (class "Default")
      (node (ref "IC201") (pin "14") (pinfunction "OP1_14") (pintype "output"))
      (node (ref "SV204") (pin "3") (pinfunction "3_3") (pintype "passive"))
    )
    (net (code "54") (name "IO_OUT5") (class "Default")
      (node (ref "IC201") (pin "16") (pinfunction "OP5_16") (pintype "output"))
      (node (ref "SV204") (pin "1") (pinfunction "1_1") (pintype "passive"))
    )
    (net (code "55") (name "Net-(C201-Pad2)") (class "Default")
      (node (ref "C201") (pin "2") (pinfunction "2_2") (pintype "passive"))
      (node (ref "Q201") (pin "2") (pinfunction "2_2") (pintype "passive"))
      (node (ref "R203") (pin "1") (pinfunction "1_1") (pintype "passive"))
    )
    (net (code "56") (name "Net-(C202-Pad2)") (class "Default")
      (node (ref "C202") (pin "2") (pinfunction "2_2") (pintype "passive"))
      (node (ref "Q201") (pin "1") (pinfunction "1_1") (pintype "passive"))
      (node (ref "R204") (pin "1") (pinfunction "1_1") (pintype "passive"))
    )
    (net (code "57") (name "Net-(IC303A-D2)") (class "Default")
      (node (ref "IC303") (pin "2") (pinfunction "Q1_2") (pintype "output"))
      (node (ref "IC303") (pin "5") (pinfunction "D2_5") (pintype "input"))
    )
    (net (code "58") (name "Net-(IC303A-D3)") (class "Default")
      (node (ref "IC303") (pin "12") (pinfunction "D3_12") (pintype "input"))
      (node (ref "IC303") (pin "7") (pinfunction "Q2_7") (pintype "output"))
    )
    (net (code "59") (name "Net-(IC303A-D4)") (class "Default")
      (node (ref "IC303") (pin "10") (pinfunction "Q3_10") (pintype "output"))
      (node (ref "IC303") (pin "13") (pinfunction "D4_13") (pintype "input"))
    )
    (net (code "60") (name "Net-(IC304-DIS)") (class "Default")
      (node (ref "C304") (pin "1") (pinfunction "1_1") (pintype "passive"))
      (node (ref "IC304") (pin "6") (pinfunction "TRE_6") (pintype "input"))
      (node (ref "IC304") (pin "7") (pinfunction "DIS_7") (pintype "input"))
      (node (ref "R302") (pin "2") (pinfunction "2_2") (pintype "passive"))
    )
    (net (code "61") (name "Net-(IC304-TRI)") (class "Default")
      (node (ref "C303") (pin "1") (pinfunction "1_1") (pintype "passive"))
      (node (ref "IC304") (pin "2") (pinfunction "TRI_2") (pintype "input"))
      (node (ref "R301") (pin "2") (pinfunction "2_2") (pintype "passive"))
      (node (ref "S301") (pin "1") (pinfunction "S_1") (pintype "passive"))
      (node (ref "S301") (pin "2") (pinfunction "S1_2") (pintype "passive"))
    )
    (net (code "62") (name "Net-(LED101-PadA)") (class "Default")
      (node (ref "LED101") (pin "A") (pinfunction "A_A") (pintype "passive"))
      (node (ref "R114") (pin "2") (pinfunction "2_2") (pintype "passive"))
    )
    (net (code "63") (name "Net-(LED201-PadA)") (class "Default")
      (node (ref "LED201") (pin "A") (pinfunction "A_A") (pintype "passive"))
      (node (ref "R205") (pin "2") (pinfunction "2_2") (pintype "passive"))
    )
    (net (code "64") (name "Net-(LED202-PadA)") (class "Default")
      (node (ref "LED202") (pin "A") (pinfunction "A_A") (pintype "passive"))
      (node (ref "R206") (pin "2") (pinfunction "2_2") (pintype "passive"))
    )
    (net (code "65") (name "RESET") (class "Default")
      (node (ref "IC302") (pin "9") (pinfunction "IN9_9") (pintype "input"))
      (node (ref "IC304") (pin "3") (pinfunction "OUT_3") (pintype "output"))
    )
    (net (code "66") (name "R{slash}~{W}") (class "Default")
      (node (ref "IC101") (pin "30") (pinfunction "R/~{W}_30") (pintype "output"))
      (node (ref "IC102") (pin "29") (pinfunction "~{WE}_29") (pintype "input"))
      (node (ref "IC103") (pin "31") (pinfunction "~{WE}_31") (pintype "input"))
      (node (ref "IC201") (pin "9") (pinfunction "R/~{W}_9") (pintype "input"))
      (node (ref "IC202") (pin "27") (pinfunction "~{WE}_27") (pintype "input"))
      (node (ref "IC301") (pin "5") (pinfunction "IN5_5") (pintype "input"))
      (node (ref "SV202") (pin "29") (pinfunction "29_29") (pintype "passive"))
    )
    (net (code "67") (name "STATUS0") (class "Default")
      (node (ref "IC201") (pin "15") (pinfunction "OP3_15") (pintype "output"))
      (node (ref "R206") (pin "1") (pinfunction "1_1") (pintype "passive"))
    )
    (net (code "68") (name "STATUS1") (class "Default")
      (node (ref "IC201") (pin "17") (pinfunction "OP7_17") (pintype "output"))
      (node (ref "R205") (pin "1") (pinfunction "1_1") (pintype "passive"))
    )
    (net (code "69") (name "UART0_RX") (class "Default")
      (node (ref "IC201") (pin "35") (pinfunction "RXDA_35") (pintype "input"))
      (node (ref "SV203") (pin "2") (pinfunction "2_2") (pintype "passive"))
    )
    (net (code "70") (name "UART0_TX") (class "Default")
      (node (ref "IC201") (pin "33") (pinfunction "TXDA_33") (pintype "output"))
      (node (ref "SV203") (pin "1") (pinfunction "1_1") (pintype "passive"))
    )
    (net (code "71") (name "UART1_RX") (class "Default")
      (node (ref "IC201") (pin "11") (pinfunction "RXDB_11") (pintype "output"))
      (node (ref "SV203") (pin "4") (pinfunction "4_4") (pintype "passive"))
    )
    (net (code "72") (name "UART1_TX") (class "Default")
      (node (ref "IC201") (pin "13") (pinfunction "TXDB_13") (pintype "bidirectional"))
      (node (ref "SV203") (pin "3") (pinfunction "3_3") (pintype "passive"))
    )
    (net (code "73") (name "unconnected-(IC301-IO21-Pad21)") (class "Default")
      (node (ref "IC301") (pin "21") (pinfunction "IO21_21") (pintype "bidirectional"))
    )
    (net (code "74") (name "unconnected-(IC302-IO14-Pad14)") (class "Default")
      (node (ref "IC302") (pin "14") (pinfunction "IO14_14") (pintype "bidirectional"))
    )
    (net (code "75") (name "unconnected-(IC302-IO15-Pad15)") (class "Default")
      (node (ref "IC302") (pin "15") (pinfunction "IO15_15") (pintype "bidirectional"))
    )
    (net (code "76") (name "unconnected-(IC302-IO16-Pad16)") (class "Default")
      (node (ref "IC302") (pin "16") (pinfunction "IO16_16") (pintype "bidirectional"))
    )
    (net (code "77") (name "unconnected-(IC303A-Q4-Pad15)") (class "Default")
      (node (ref "IC303") (pin "15") (pinfunction "Q4_15") (pintype "output"))
    )
    (net (code "78") (name "unconnected-(IC303A-~{Q1}-Pad3)") (class "Default")
      (node (ref "IC303") (pin "3") (pinfunction "~{Q1}_3") (pintype "output"))
    )
    (net (code "79") (name "unconnected-(IC303A-~{Q2}-Pad6)") (class "Default")
      (node (ref "IC303") (pin "6") (pinfunction "~{Q2}_6") (pintype "output"))
    )
    (net (code "80") (name "unconnected-(IC303A-~{Q3}-Pad11)") (class "Default")
      (node (ref "IC303") (pin "11") (pinfunction "~{Q3}_11") (pintype "output"))
    )
    (net (code "81") (name "unconnected-(Q101-TS-Pad1)") (class "Default")
      (node (ref "Q101") (pin "1") (pinfunction "TS_1") (pintype "passive"))
    )
    (net (code "82") (name "~{68681_CS}") (class "Default")
      (node (ref "IC201") (pin "39") (pinfunction "~{CS}_39") (pintype "input"))
      (node (ref "IC301") (pin "14") (pinfunction "IO14_14") (pintype "bidirectional"))
    )
    (net (code "83") (name "~{68681_DTACK}") (class "Default")
      (node (ref "IC201") (pin "10") (pinfunction "~{DTACK}_10") (pintype "output"))
      (node (ref "IC302") (pin "11") (pinfunction "IN11_11") (pintype "input"))
      (node (ref "R201") (pin "1") (pinfunction "1_1") (pintype "passive"))
    )
    (net (code "84") (name "~{68681_IACK}") (class "Default")
      (node (ref "IC201") (pin "41") (pinfunction "~{IACK}_41") (pintype "input"))
      (node (ref "IC302") (pin "10") (pinfunction "IN10_10") (pintype "input"))
    )
    (net (code "85") (name "~{68681_IRQ}") (class "Default")
      (node (ref "IC201") (pin "24") (pinfunction "~{INTR}_24") (pintype "output"))
      (node (ref "IC302") (pin "13") (pinfunction "IN13_13") (pintype "input"))
      (node (ref "R202") (pin "1") (pinfunction "1_1") (pintype "passive"))
    )
    (net (code "86") (name "~{AS}") (class "Default")
      (node (ref "IC101") (pin "28") (pinfunction "AS_28") (pintype "output"))
      (node (ref "IC301") (pin "6") (pinfunction "IN6_6") (pintype "input"))
      (node (ref "SV202") (pin "33") (pinfunction "33_33") (pintype "passive"))
    )
    (net (code "87") (name "~{BERR_TIMER_CLR}") (class "Default")
      (node (ref "IC301") (pin "22") (pinfunction "IO22_22") (pintype "bidirectional"))
      (node (ref "IC303") (pin "1") (pinfunction "CLR_1") (pintype "input"))
    )
    (net (code "88") (name "~{BERR}") (class "Default")
      (node (ref "IC101") (pin "40") (pinfunction "BERR_40") (pintype "input"))
      (node (ref "IC302") (pin "17") (pinfunction "IO17_17") (pintype "bidirectional"))
      (node (ref "IC303") (pin "14") (pinfunction "~{Q4}_14") (pintype "output"))
      (node (ref "R113") (pin "2") (pinfunction "2_2") (pintype "passive"))
      (node (ref "SV202") (pin "9") (pinfunction "9_9") (pintype "passive"))
    )
    (net (code "89") (name "~{BG}") (class "Default")
      (node (ref "IC101") (pin "32") (pinfunction "BG_32") (pintype "output"))
      (node (ref "SV202") (pin "25") (pinfunction "25_25") (pintype "passive"))
    )
    (net (code "90") (name "~{BR}") (class "Default")
      (node (ref "IC101") (pin "33") (pinfunction "BR_33") (pintype "input"))
      (node (ref "R111") (pin "2") (pinfunction "2_2") (pintype "passive"))
      (node (ref "SV202") (pin "23") (pinfunction "23_23") (pintype "passive"))
    )
    (net (code "91") (name "~{BUS_CS}") (class "Default")
      (node (ref "IC301") (pin "23") (pinfunction "IO23_23") (pintype "bidirectional"))
      (node (ref "SV201") (pin "7") (pinfunction "7_7") (pintype "passive"))
    )
    (net (code "92") (name "~{BUS_DTACK}") (class "Default")
      (node (ref "IC302") (pin "4") (pinfunction "IN4_4") (pintype "input"))
      (node (ref "SV201") (pin "6") (pinfunction "6_6") (pintype "passive"))
    )
    (net (code "93") (name "~{BUS_IRQ}") (class "Default")
      (node (ref "IC302") (pin "5") (pinfunction "IN5_5") (pintype "input"))
      (node (ref "SV201") (pin "5") (pinfunction "5_5") (pintype "passive"))
    )
    (net (code "94") (name "~{DS}") (class "Default")
      (node (ref "IC101") (pin "29") (pinfunction "DS_29") (pintype "output"))
      (node (ref "SV202") (pin "31") (pinfunction "31_31") (pintype "passive"))
    )
    (net (code "95") (name "~{DTACK}") (class "Default")
      (node (ref "IC101") (pin "31") (pinfunction "DTACK_31") (pintype "input"))
      (node (ref "IC302") (pin "20") (pinfunction "IO20_20") (pintype "bidirectional"))
      (node (ref "SV202") (pin "27") (pinfunction "27_27") (pintype "passive"))
    )
    (net (code "96") (name "~{HALT}") (class "Default")
      (node (ref "IC101") (pin "36") (pinfunction "HALT_36") (pintype "bidirectional"))
      (node (ref "IC302") (pin "21") (pinfunction "IO21_21") (pintype "bidirectional"))
      (node (ref "R102") (pin "1") (pinfunction "1_1") (pintype "passive"))
      (node (ref "SV202") (pin "17") (pinfunction "17_17") (pintype "passive"))
    )
    (net (code "97") (name "~{IACK}") (class "Default")
      (node (ref "IC301") (pin "19") (pinfunction "IO19_19") (pintype "bidirectional"))
      (node (ref "IC302") (pin "7") (pinfunction "IN7_7") (pintype "input"))
    )
    (net (code "98") (name "~{IPL0{slash}2}") (class "Default")
      (node (ref "IC101") (pin "42") (pinfunction "IPL0/2_42") (pintype "input"))
      (node (ref "IC302") (pin "19") (pinfunction "IO19_19") (pintype "bidirectional"))
    )
    (net (code "99") (name "~{IPL1}") (class "Default")
      (node (ref "IC101") (pin "41") (pinfunction "IPL1_41") (pintype "input"))
      (node (ref "IC302") (pin "18") (pinfunction "IO18_18") (pintype "bidirectional"))
    )
    (net (code "100") (name "~{OE}") (class "Default")
      (node (ref "IC102") (pin "24") (pinfunction "~{OE}_24") (pintype "input"))
      (node (ref "IC103") (pin "24") (pinfunction "~{OE}_24") (pintype "input"))
      (node (ref "IC202") (pin "22") (pinfunction "~{OE}_22") (pintype "input"))
      (node (ref "IC301") (pin "18") (pinfunction "IO18_18") (pintype "bidirectional"))
    )
    (net (code "101") (name "~{RAM_CS}") (class "Default")
      (node (ref "IC102") (pin "22") (pinfunction "~{CE1}_22") (pintype "input"))
      (node (ref "IC301") (pin "16") (pinfunction "IO16_16") (pintype "bidirectional"))
    )
    (net (code "102") (name "~{REQUIRE_DTACK}") (class "Default")
      (node (ref "IC301") (pin "20") (pinfunction "IO20_20") (pintype "bidirectional"))
      (node (ref "IC302") (pin "6") (pinfunction "IN6_6") (pintype "input"))
    )
    (net (code "103") (name "~{RESET}") (class "Default")
      (node (ref "IC101") (pin "37") (pinfunction "RESET_37") (pintype "bidirectional"))
      (node (ref "IC201") (pin "38") (pinfunction "~{RESET}_38") (pintype "input"))
      (node (ref "IC302") (pin "22") (pinfunction "IO22_22") (pintype "bidirectional"))
      (node (ref "R101") (pin "1") (pinfunction "1_1") (pintype "passive"))
      (node (ref "SV202") (pin "15") (pinfunction "15_15") (pintype "passive"))
    )
    (net (code "104") (name "~{ROM_CS}") (class "Default")
      (node (ref "IC103") (pin "22") (pinfunction "~{CS}_22") (pintype "input"))
      (node (ref "IC301") (pin "17") (pinfunction "IO17_17") (pintype "bidirectional"))
    )
    (net (code "105") (name "~{RTC_CS}") (class "Default")
      (node (ref "IC202") (pin "20") (pinfunction "~{CS}_20") (pintype "input"))
      (node (ref "IC301") (pin "15") (pinfunction "IO15_15") (pintype "bidirectional"))
    )
    (net (code "106") (name "~{VPA}") (class "Default")
      (node (ref "IC101") (pin "39") (pinfunction "VPA_39") (pintype "input"))
      (node (ref "IC302") (pin "23") (pinfunction "IO23_23") (pintype "bidirectional"))
      (node (ref "R112") (pin "2") (pinfunction "2_2") (pintype "passive"))
      (node (ref "SV202") (pin "11") (pinfunction "11_11") (pintype "passive"))
    )
  )
)
